# pcb.net
KiCad netlist of a schematic drawn in EasyEDA
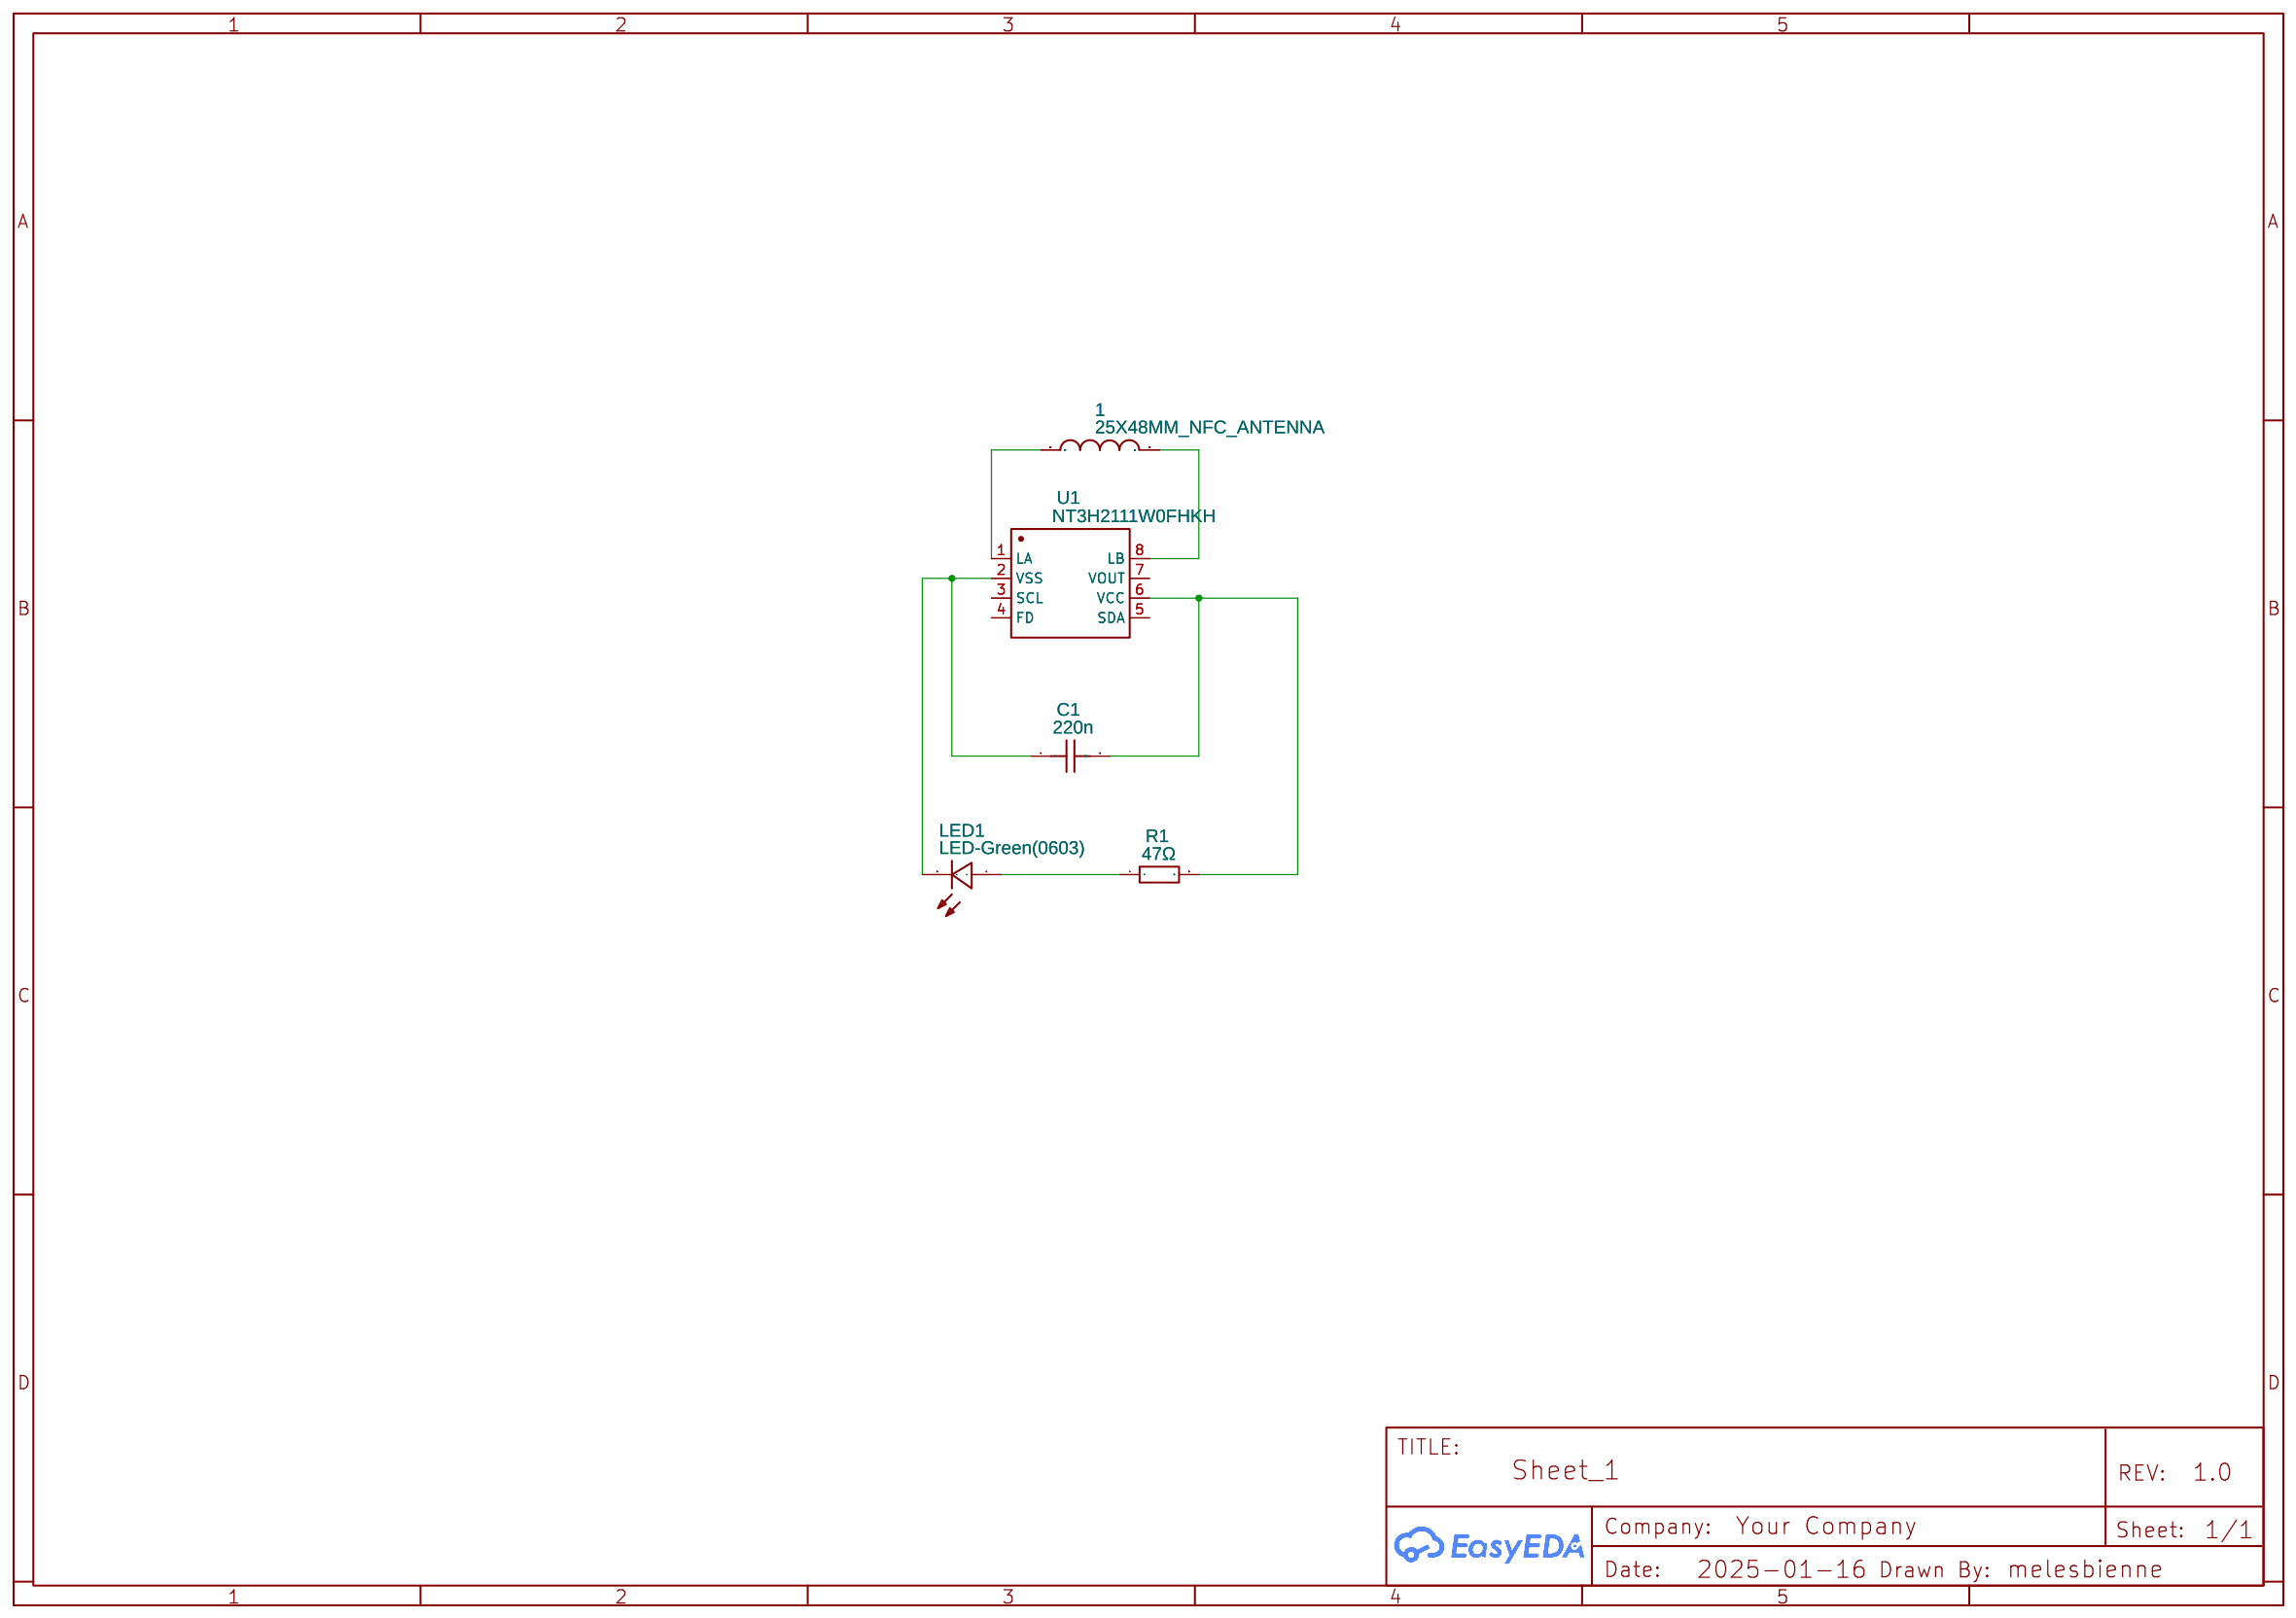
[diagram p0: schematic sheet]

(export (version "E")
  (design (tool "Eeschema 10.0.6"))
  (components
    (comp (ref "1") (value "25X48MM_NFC_ANTENNA") (libsource (lib "") (part "25X48MM_NFC_ANTENNA")))
    (comp (ref "C1") (value "220n") (libsource (lib "") (part "C_0603_US")))
    (comp (ref "LED1")
      (value "LED-Green(0603)")
      (fields
        (field (name "Manufacturer Part") "FC-DA1608UGK-520D10")
        (field (name "Manufacturer") "Foshan NationStar Optoelectronics")
      )
      (libsource (lib "") (part "LED-Green(0603)"))
    )
    (comp (ref "R1")
      (value "47Ω")
      (fields
        (field (name "Manufacturer Part") "0603WAF470JT5E")
        (field (name "Manufacturer") "UNI-ROYAL(厚声)")
      )
      (libsource (lib "") (part "0603WAF470JT5E"))
    )
    (comp (ref "U1")
      (value "NT3H2111W0FHKH")
      (fields (field (name "Manufacturer") "NXP(恩智浦)"))
      (libsource (lib "") (part "NT3H2111W0FHKH"))
    )
  )
  (nets
    (net (code "1") (name "Net-(LED1-+)") (class "Default")
      (node (ref "LED1") (pin "1") (pinfunction "+_1") (pintype "unspecified"))
      (node (ref "R1") (pin "1") (pinfunction "1_1") (pintype "input"))
    )
    (net (code "2") (name "Net-(LED1--)") (class "Default")
      (node (ref "C1") (pin "1") (pinfunction "1_1") (pintype "unspecified"))
      (node (ref "LED1") (pin "2") (pinfunction "-_2") (pintype "unspecified"))
      (node (ref "U1") (pin "2") (pinfunction "VSS_2") (pintype "unspecified"))
    )
    (net (code "3") (name "Net-(U1-LA)") (class "Default")
      (node (ref "1") (pin "P$1") (pinfunction "P$1_P$1") (pintype "bidirectional"))
      (node (ref "U1") (pin "1") (pinfunction "LA_1") (pintype "unspecified"))
    )
    (net (code "4") (name "Net-(U1-LB)") (class "Default")
      (node (ref "1") (pin "P$2") (pinfunction "P$2_P$2") (pintype "bidirectional"))
      (node (ref "U1") (pin "8") (pinfunction "LB_8") (pintype "unspecified"))
    )
    (net (code "5") (name "Net-(U1-VCC)") (class "Default")
      (node (ref "C1") (pin "2") (pinfunction "2_2") (pintype "unspecified"))
      (node (ref "R1") (pin "2") (pinfunction "2_2") (pintype "input"))
      (node (ref "U1") (pin "6") (pinfunction "VCC_6") (pintype "unspecified"))
    )
    (net (code "6") (name "unconnected-(U1-FD-Pad4)") (class "Default")
      (node (ref "U1") (pin "4") (pinfunction "FD_4") (pintype "unspecified"))
    )
    (net (code "7") (name "unconnected-(U1-SCL-Pad3)") (class "Default")
      (node (ref "U1") (pin "3") (pinfunction "SCL_3") (pintype "unspecified"))
    )
    (net (code "8") (name "unconnected-(U1-SDA-Pad5)") (class "Default")
      (node (ref "U1") (pin "5") (pinfunction "SDA_5") (pintype "unspecified"))
    )
    (net (code "9") (name "unconnected-(U1-VOUT-Pad7)") (class "Default")
      (node (ref "U1") (pin "7") (pinfunction "VOUT_7") (pintype "unspecified"))
    )
  )
)
